# TrackerBaseStation.net
KiCad netlist of a schematic drawn in EAGLE
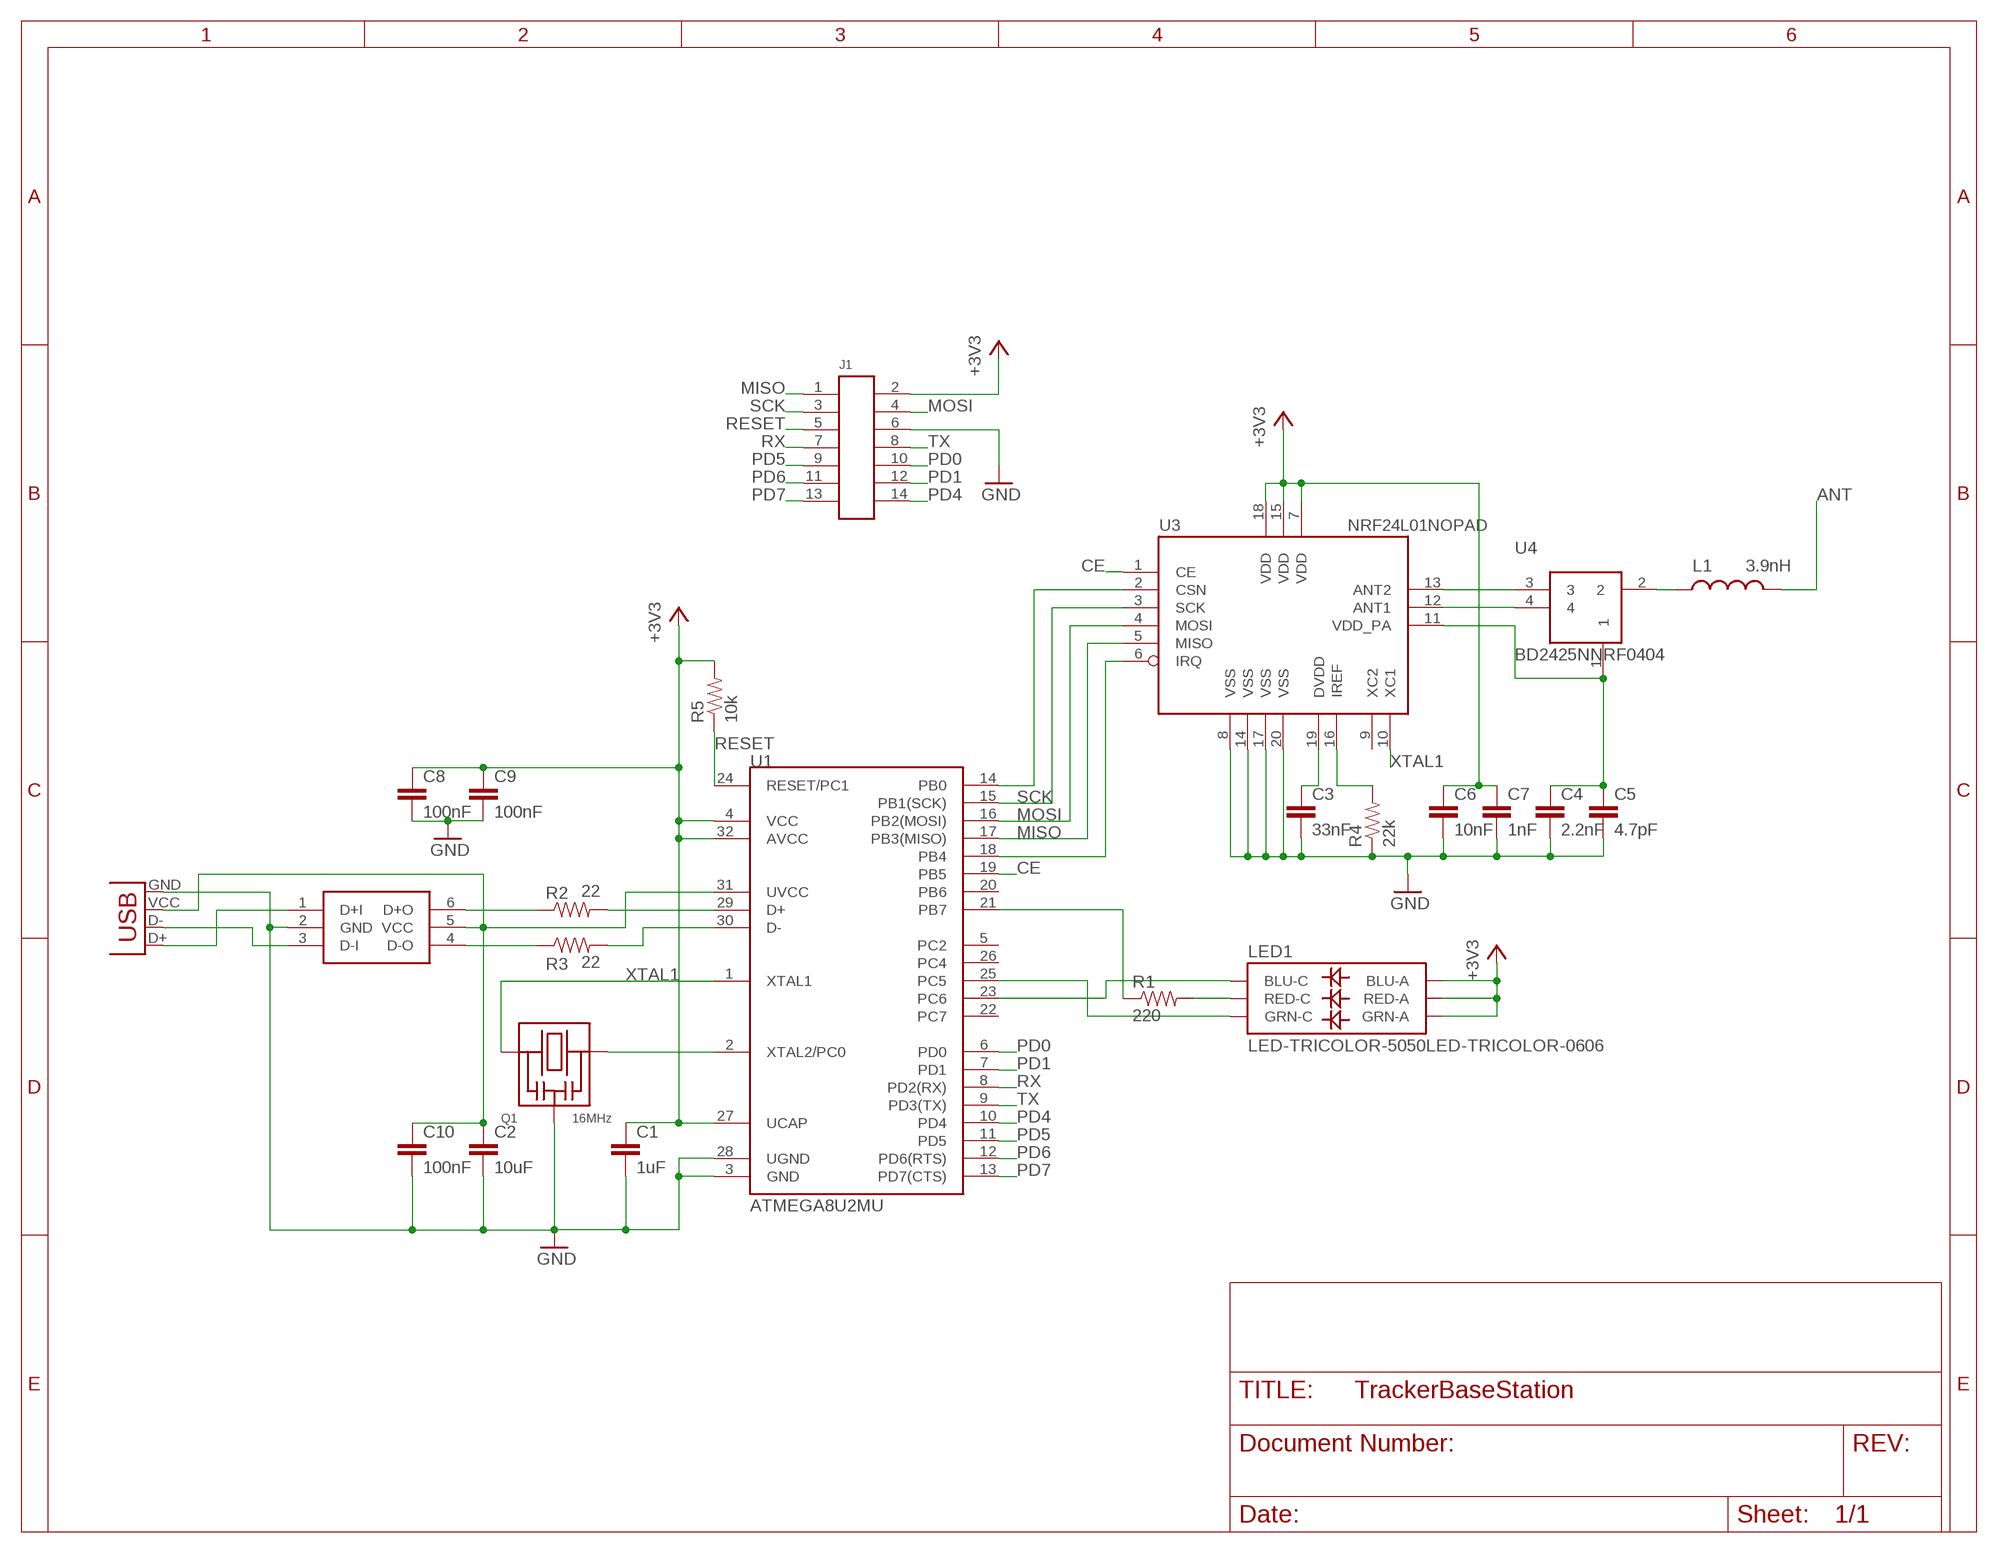
[diagram p0: schematic, sheet 1]

(export (version "E")
  (design (tool "Eeschema 10.0.6"))
  (components
    (comp (ref "C1")
      (value "1uF")
      (footprint "eagle-import:0402-CAP")
      (libsource (lib "eagle-import") (part "SparkFun-Passives_CAP0402-CAP"))
    )
    (comp (ref "C2")
      (value "10uF")
      (footprint "eagle-import:0603-CAP")
      (libsource (lib "eagle-import") (part "SparkFun-Passives_CAP0603-CAP"))
    )
    (comp (ref "C3")
      (value "33nF")
      (footprint "eagle-import:0402-CAP")
      (libsource (lib "eagle-import") (part "SparkFun-Passives_CAP0402-CAP"))
    )
    (comp (ref "C4")
      (value "2.2nF")
      (footprint "eagle-import:0402-CAP")
      (libsource (lib "eagle-import") (part "CAP0402-CAP"))
    )
    (comp (ref "C5")
      (value "4.7pF")
      (footprint "eagle-import:0402-CAP")
      (libsource (lib "eagle-import") (part "CAP0402-CAP"))
    )
    (comp (ref "C6")
      (value "10nF")
      (footprint "eagle-import:0402-CAP")
      (libsource (lib "eagle-import") (part "CAP0402-CAP"))
    )
    (comp (ref "C7")
      (value "1nF")
      (footprint "eagle-import:0402-CAP")
      (libsource (lib "eagle-import") (part "CAP0402-CAP"))
    )
    (comp (ref "C8")
      (value "100nF")
      (footprint "eagle-import:0402-CAP")
      (libsource (lib "eagle-import") (part "SparkFun-Passives_CAP0402-CAP"))
    )
    (comp (ref "C9")
      (value "100nF")
      (footprint "eagle-import:0402-CAP")
      (libsource (lib "eagle-import") (part "SparkFun-Passives_CAP0402-CAP"))
    )
    (comp (ref "C10")
      (value "100nF")
      (footprint "eagle-import:0402-CAP")
      (libsource (lib "eagle-import") (part "SparkFun-Passives_CAP0402-CAP"))
    )
    (comp (ref "J1")
      (value "DF12A3.0-14DS")
      (footprint "eagle-import:DF12A3.0-14DS")
      (libsource (lib "eagle-import") (part "DF12A3.0-14DS"))
    )
    (comp (ref "L1")
      (value "3.9nH")
      (footprint "eagle-import:C0402")
      (libsource (lib "eagle-import") (part "INDUCTOR0402"))
    )
    (comp (ref "LED1")
      (value "LED-TRICOLOR-5050LED-TRICOLOR-0606")
      (footprint "eagle-import:0606")
      (libsource (lib "eagle-import") (part "LED-TRICOLOR-5050LED-TRICOLOR-0606"))
    )
    (comp (ref "Q1")
      (value "16MHz")
      (footprint "eagle-import:PRQC")
      (libsource (lib "eagle-import") (part "RESONATORPRQC"))
    )
    (comp (ref "R1")
      (value "220")
      (footprint "eagle-import:0402-RES")
      (libsource (lib "eagle-import") (part "RESISTOR0402-RES"))
    )
    (comp (ref "R2")
      (value "22")
      (footprint "eagle-import:0402-RES")
      (libsource (lib "eagle-import") (part "RESISTOR0402-RES"))
    )
    (comp (ref "R3")
      (value "22")
      (footprint "eagle-import:0402-RES")
      (libsource (lib "eagle-import") (part "RESISTOR0402-RES"))
    )
    (comp (ref "R4")
      (value "22k")
      (footprint "eagle-import:0402-RES")
      (libsource (lib "eagle-import") (part "RESISTOR0402-RES"))
    )
    (comp (ref "R5")
      (value "10k")
      (footprint "eagle-import:0402-RES")
      (libsource (lib "eagle-import") (part "RESISTOR0402-RES"))
    )
    (comp (ref "U1")
      (value "ATMEGA8U2MU")
      (footprint "eagle-import:QFN32")
      (libsource (lib "eagle-import") (part "ATMEGA8U2MU"))
    )
    (comp (ref "U2")
      (value "RCLAMP0502A")
      (footprint "eagle-import:SOT-666")
      (libsource (lib "eagle-import") (part "RCLAMP0502A"))
    )
    (comp (ref "U3")
      (value "NRF24L01NOPAD")
      (footprint "eagle-import:QFN20-NOPAD")
      (libsource (lib "eagle-import") (part "NRF24L01NOPAD"))
    )
    (comp (ref "U4")
      (value "BD2425NNRF0404")
      (footprint "eagle-import:BD2425NNRF")
      (libsource (lib "eagle-import") (part "BD2425NNRF0404"))
    )
    (comp (ref "X1")
      (value "USB-LEG")
      (footprint "eagle-import:USB-A-SMD-LEG")
      (libsource (lib "eagle-import") (part "USB-LEG"))
    )
  )
  (nets
    (net (code "1") (name "+3V3") (class "Default")
      (node (ref "C1") (pin "1") (pinfunction "1_1") (pintype "passive"))
      (node (ref "C6") (pin "1") (pinfunction "1_1") (pintype "passive"))
      (node (ref "C7") (pin "1") (pinfunction "1_1") (pintype "passive"))
      (node (ref "C8") (pin "1") (pinfunction "1_1") (pintype "passive"))
      (node (ref "C9") (pin "1") (pinfunction "1_1") (pintype "passive"))
      (node (ref "J1") (pin "2") (pinfunction "2_2") (pintype "bidirectional"))
      (node (ref "LED1") (pin "4") (pinfunction "BLU-A_4") (pintype "bidirectional"))
      (node (ref "LED1") (pin "5") (pinfunction "RED-A_5") (pintype "bidirectional"))
      (node (ref "LED1") (pin "6") (pinfunction "GRN-A_6") (pintype "bidirectional"))
      (node (ref "R5") (pin "2") (pinfunction "2_2") (pintype "passive"))
      (node (ref "U1") (pin "27") (pinfunction "UCAP_27") (pintype "bidirectional"))
      (node (ref "U1") (pin "32") (pinfunction "AVCC_32") (pintype "bidirectional"))
      (node (ref "U1") (pin "4") (pinfunction "VCC_4") (pintype "bidirectional"))
      (node (ref "U3") (pin "15") (pinfunction "VDD_15") (pintype "power_in"))
      (node (ref "U3") (pin "18") (pinfunction "VDD_18") (pintype "power_in"))
      (node (ref "U3") (pin "7") (pinfunction "VDD_7") (pintype "power_in"))
    )
    (net (code "2") (name "/ANT") (class "Default")
      (node (ref "L1") (pin "2") (pinfunction "2_2") (pintype "passive"))
    )
    (net (code "3") (name "/CE") (class "Default")
      (node (ref "U1") (pin "19") (pinfunction "PB5_19") (pintype "bidirectional"))
      (node (ref "U3") (pin "1") (pinfunction "CE_1") (pintype "input"))
    )
    (net (code "4") (name "/MISO") (class "Default")
      (node (ref "J1") (pin "1") (pinfunction "1_1") (pintype "bidirectional"))
      (node (ref "U1") (pin "17") (pinfunction "PB3(MISO)_17") (pintype "bidirectional"))
      (node (ref "U3") (pin "5") (pinfunction "MISO_5") (pintype "output"))
    )
    (net (code "5") (name "/MOSI") (class "Default")
      (node (ref "J1") (pin "4") (pinfunction "4_4") (pintype "bidirectional"))
      (node (ref "U1") (pin "16") (pinfunction "PB2(MOSI)_16") (pintype "bidirectional"))
      (node (ref "U3") (pin "4") (pinfunction "MOSI_4") (pintype "input"))
    )
    (net (code "6") (name "/PD0") (class "Default")
      (node (ref "J1") (pin "10") (pinfunction "10_10") (pintype "bidirectional"))
      (node (ref "U1") (pin "6") (pinfunction "PD0_6") (pintype "bidirectional"))
    )
    (net (code "7") (name "/PD1") (class "Default")
      (node (ref "J1") (pin "12") (pinfunction "12_12") (pintype "bidirectional"))
      (node (ref "U1") (pin "7") (pinfunction "PD1_7") (pintype "bidirectional"))
    )
    (net (code "8") (name "/PD4") (class "Default")
      (node (ref "J1") (pin "14") (pinfunction "14_14") (pintype "bidirectional"))
      (node (ref "U1") (pin "10") (pinfunction "PD4_10") (pintype "bidirectional"))
    )
    (net (code "9") (name "/PD5") (class "Default")
      (node (ref "J1") (pin "9") (pinfunction "9_9") (pintype "bidirectional"))
      (node (ref "U1") (pin "11") (pinfunction "PD5_11") (pintype "bidirectional"))
    )
    (net (code "10") (name "/PD6") (class "Default")
      (node (ref "J1") (pin "11") (pinfunction "11_11") (pintype "bidirectional"))
      (node (ref "U1") (pin "12") (pinfunction "PD6(RTS)_12") (pintype "bidirectional"))
    )
    (net (code "11") (name "/PD7") (class "Default")
      (node (ref "J1") (pin "13") (pinfunction "13_13") (pintype "bidirectional"))
      (node (ref "U1") (pin "13") (pinfunction "PD7(CTS)_13") (pintype "bidirectional"))
    )
    (net (code "12") (name "/RESET") (class "Default")
      (node (ref "J1") (pin "5") (pinfunction "5_5") (pintype "bidirectional"))
      (node (ref "R5") (pin "1") (pinfunction "1_1") (pintype "passive"))
      (node (ref "U1") (pin "24") (pinfunction "RESET/PC1_24") (pintype "bidirectional"))
    )
    (net (code "13") (name "/RX") (class "Default")
      (node (ref "J1") (pin "7") (pinfunction "7_7") (pintype "bidirectional"))
      (node (ref "U1") (pin "8") (pinfunction "PD2(RX)_8") (pintype "bidirectional"))
    )
    (net (code "14") (name "/SCK") (class "Default")
      (node (ref "J1") (pin "3") (pinfunction "3_3") (pintype "bidirectional"))
      (node (ref "U1") (pin "15") (pinfunction "PB1(SCK)_15") (pintype "bidirectional"))
      (node (ref "U3") (pin "3") (pinfunction "SCK_3") (pintype "input"))
    )
    (net (code "15") (name "/TX") (class "Default")
      (node (ref "J1") (pin "8") (pinfunction "8_8") (pintype "bidirectional"))
      (node (ref "U1") (pin "9") (pinfunction "PD3(TX)_9") (pintype "bidirectional"))
    )
    (net (code "16") (name "/XTAL1") (class "Default")
      (node (ref "Q1") (pin "P$1") (pinfunction "1_P$1") (pintype "bidirectional"))
      (node (ref "U1") (pin "1") (pinfunction "XTAL1_1") (pintype "bidirectional"))
      (node (ref "U3") (pin "10") (pinfunction "XC1_10") (pintype "input"))
    )
    (net (code "17") (name "GND") (class "Default")
      (node (ref "C1") (pin "2") (pinfunction "2_2") (pintype "passive"))
      (node (ref "C10") (pin "2") (pinfunction "2_2") (pintype "passive"))
      (node (ref "C2") (pin "2") (pinfunction "2_2") (pintype "passive"))
      (node (ref "C3") (pin "2") (pinfunction "2_2") (pintype "passive"))
      (node (ref "C4") (pin "2") (pinfunction "2_2") (pintype "passive"))
      (node (ref "C5") (pin "2") (pinfunction "2_2") (pintype "passive"))
      (node (ref "C6") (pin "2") (pinfunction "2_2") (pintype "passive"))
      (node (ref "C7") (pin "2") (pinfunction "2_2") (pintype "passive"))
      (node (ref "C8") (pin "2") (pinfunction "2_2") (pintype "passive"))
      (node (ref "C9") (pin "2") (pinfunction "2_2") (pintype "passive"))
      (node (ref "J1") (pin "6") (pinfunction "6_6") (pintype "bidirectional"))
      (node (ref "Q1") (pin "P$2") (pinfunction "GND_P$2") (pintype "power_in"))
      (node (ref "R4") (pin "1") (pinfunction "1_1") (pintype "passive"))
      (node (ref "U1") (pin "28") (pinfunction "UGND_28") (pintype "bidirectional"))
      (node (ref "U1") (pin "3") (pinfunction "GND_3") (pintype "bidirectional"))
      (node (ref "U2") (pin "2") (pinfunction "GND_2") (pintype "bidirectional"))
      (node (ref "U3") (pin "14") (pinfunction "VSS_14") (pintype "power_in"))
      (node (ref "U3") (pin "17") (pinfunction "VSS_17") (pintype "power_in"))
      (node (ref "U3") (pin "20") (pinfunction "VSS_20") (pintype "power_in"))
      (node (ref "U3") (pin "8") (pinfunction "VSS_8") (pintype "power_in"))
      (node (ref "X1") (pin "GND") (pinfunction "GND_GND") (pintype "bidirectional"))
    )
    (net (code "18") (name "Net-(L1-Pad1)") (class "Default")
      (node (ref "L1") (pin "1") (pinfunction "1_1") (pintype "passive"))
      (node (ref "U4") (pin "2") (pinfunction "2_2") (pintype "bidirectional"))
    )
    (net (code "19") (name "Net-(LED1-BLU-C)") (class "Default")
      (node (ref "LED1") (pin "1") (pinfunction "BLU-C_1") (pintype "bidirectional"))
      (node (ref "U1") (pin "23") (pinfunction "PC6_23") (pintype "bidirectional"))
    )
    (net (code "20") (name "Net-(LED1-GRN-C)") (class "Default")
      (node (ref "LED1") (pin "3") (pinfunction "GRN-C_3") (pintype "bidirectional"))
      (node (ref "U1") (pin "25") (pinfunction "PC5_25") (pintype "bidirectional"))
    )
    (net (code "21") (name "Net-(LED1-RED-C)") (class "Default")
      (node (ref "LED1") (pin "2") (pinfunction "RED-C_2") (pintype "bidirectional"))
      (node (ref "R1") (pin "2") (pinfunction "2_2") (pintype "passive"))
    )
    (net (code "22") (name "Net-(Q1-2)") (class "Default")
      (node (ref "Q1") (pin "P$3") (pinfunction "2_P$3") (pintype "bidirectional"))
      (node (ref "U1") (pin "2") (pinfunction "XTAL2/PC0_2") (pintype "bidirectional"))
    )
    (net (code "23") (name "Net-(U1-D+)") (class "Default")
      (node (ref "R2") (pin "2") (pinfunction "2_2") (pintype "passive"))
      (node (ref "U1") (pin "29") (pinfunction "D+_29") (pintype "bidirectional"))
    )
    (net (code "24") (name "Net-(U1-D-)") (class "Default")
      (node (ref "R3") (pin "2") (pinfunction "2_2") (pintype "passive"))
      (node (ref "U1") (pin "30") (pinfunction "D-_30") (pintype "bidirectional"))
    )
    (net (code "25") (name "Net-(U1-PB0)") (class "Default")
      (node (ref "U1") (pin "14") (pinfunction "PB0_14") (pintype "bidirectional"))
      (node (ref "U3") (pin "2") (pinfunction "CSN_2") (pintype "input"))
    )
    (net (code "26") (name "Net-(U1-PB4)") (class "Default")
      (node (ref "U1") (pin "18") (pinfunction "PB4_18") (pintype "bidirectional"))
      (node (ref "U3") (pin "6") (pinfunction "IRQ_6") (pintype "output"))
    )
    (net (code "27") (name "Net-(U1-PB7)") (class "Default")
      (node (ref "R1") (pin "1") (pinfunction "1_1") (pintype "passive"))
      (node (ref "U1") (pin "21") (pinfunction "PB7_21") (pintype "bidirectional"))
    )
    (net (code "28") (name "Net-(U1-UVCC)") (class "Default")
      (node (ref "C10") (pin "1") (pinfunction "1_1") (pintype "passive"))
      (node (ref "C2") (pin "1") (pinfunction "1_1") (pintype "passive"))
      (node (ref "U1") (pin "31") (pinfunction "UVCC_31") (pintype "bidirectional"))
      (node (ref "U2") (pin "5") (pinfunction "VCC_5") (pintype "bidirectional"))
      (node (ref "X1") (pin "VCC") (pinfunction "VBUS_VCC") (pintype "bidirectional"))
    )
    (net (code "29") (name "Net-(U2-D+I)") (class "Default")
      (node (ref "U2") (pin "1") (pinfunction "D+I_1") (pintype "bidirectional"))
      (node (ref "X1") (pin "D+") (pinfunction "D+_D+") (pintype "bidirectional"))
    )
    (net (code "30") (name "Net-(U2-D+O)") (class "Default")
      (node (ref "R2") (pin "1") (pinfunction "1_1") (pintype "passive"))
      (node (ref "U2") (pin "6") (pinfunction "D+O_6") (pintype "bidirectional"))
    )
    (net (code "31") (name "Net-(U2-D-I)") (class "Default")
      (node (ref "U2") (pin "3") (pinfunction "D-I_3") (pintype "bidirectional"))
      (node (ref "X1") (pin "D-") (pinfunction "D-_D-") (pintype "bidirectional"))
    )
    (net (code "32") (name "Net-(U2-D-O)") (class "Default")
      (node (ref "R3") (pin "1") (pinfunction "1_1") (pintype "passive"))
      (node (ref "U2") (pin "4") (pinfunction "D-O_4") (pintype "bidirectional"))
    )
    (net (code "33") (name "Net-(U3-ANT1)") (class "Default")
      (node (ref "U3") (pin "12") (pinfunction "ANT1_12") (pintype "output"))
      (node (ref "U4") (pin "4") (pinfunction "4_4") (pintype "bidirectional"))
    )
    (net (code "34") (name "Net-(U3-ANT2)") (class "Default")
      (node (ref "U3") (pin "13") (pinfunction "ANT2_13") (pintype "output"))
      (node (ref "U4") (pin "3") (pinfunction "3_3") (pintype "bidirectional"))
    )
    (net (code "35") (name "Net-(U3-DVDD)") (class "Default")
      (node (ref "C3") (pin "1") (pinfunction "1_1") (pintype "passive"))
      (node (ref "U3") (pin "19") (pinfunction "DVDD_19") (pintype "power_in"))
    )
    (net (code "36") (name "Net-(U3-IREF)") (class "Default")
      (node (ref "R4") (pin "2") (pinfunction "2_2") (pintype "passive"))
      (node (ref "U3") (pin "16") (pinfunction "IREF_16") (pintype "input"))
    )
    (net (code "37") (name "Net-(U3-VDD_PA)") (class "Default")
      (node (ref "C4") (pin "1") (pinfunction "1_1") (pintype "passive"))
      (node (ref "C5") (pin "1") (pinfunction "1_1") (pintype "passive"))
      (node (ref "U3") (pin "11") (pinfunction "VDD_PA_11") (pintype "power_in"))
      (node (ref "U4") (pin "1") (pinfunction "1_1") (pintype "bidirectional"))
    )
    (net (code "38") (name "unconnected-(U1-PB6-Pad20)") (class "Default")
      (node (ref "U1") (pin "20") (pinfunction "PB6_20") (pintype "bidirectional"))
    )
    (net (code "39") (name "unconnected-(U1-PC2-Pad5)") (class "Default")
      (node (ref "U1") (pin "5") (pinfunction "PC2_5") (pintype "bidirectional"))
    )
    (net (code "40") (name "unconnected-(U1-PC4-Pad26)") (class "Default")
      (node (ref "U1") (pin "26") (pinfunction "PC4_26") (pintype "bidirectional"))
    )
    (net (code "41") (name "unconnected-(U1-PC7-Pad22)") (class "Default")
      (node (ref "U1") (pin "22") (pinfunction "PC7_22") (pintype "bidirectional"))
    )
    (net (code "42") (name "unconnected-(U3-XC2-Pad9)") (class "Default")
      (node (ref "U3") (pin "9") (pinfunction "XC2_9") (pintype "input"))
    )
  )
)
